# 608_donkey_030101_AllDirections.net
KiCad netlist of a schematic drawn in EAGLE
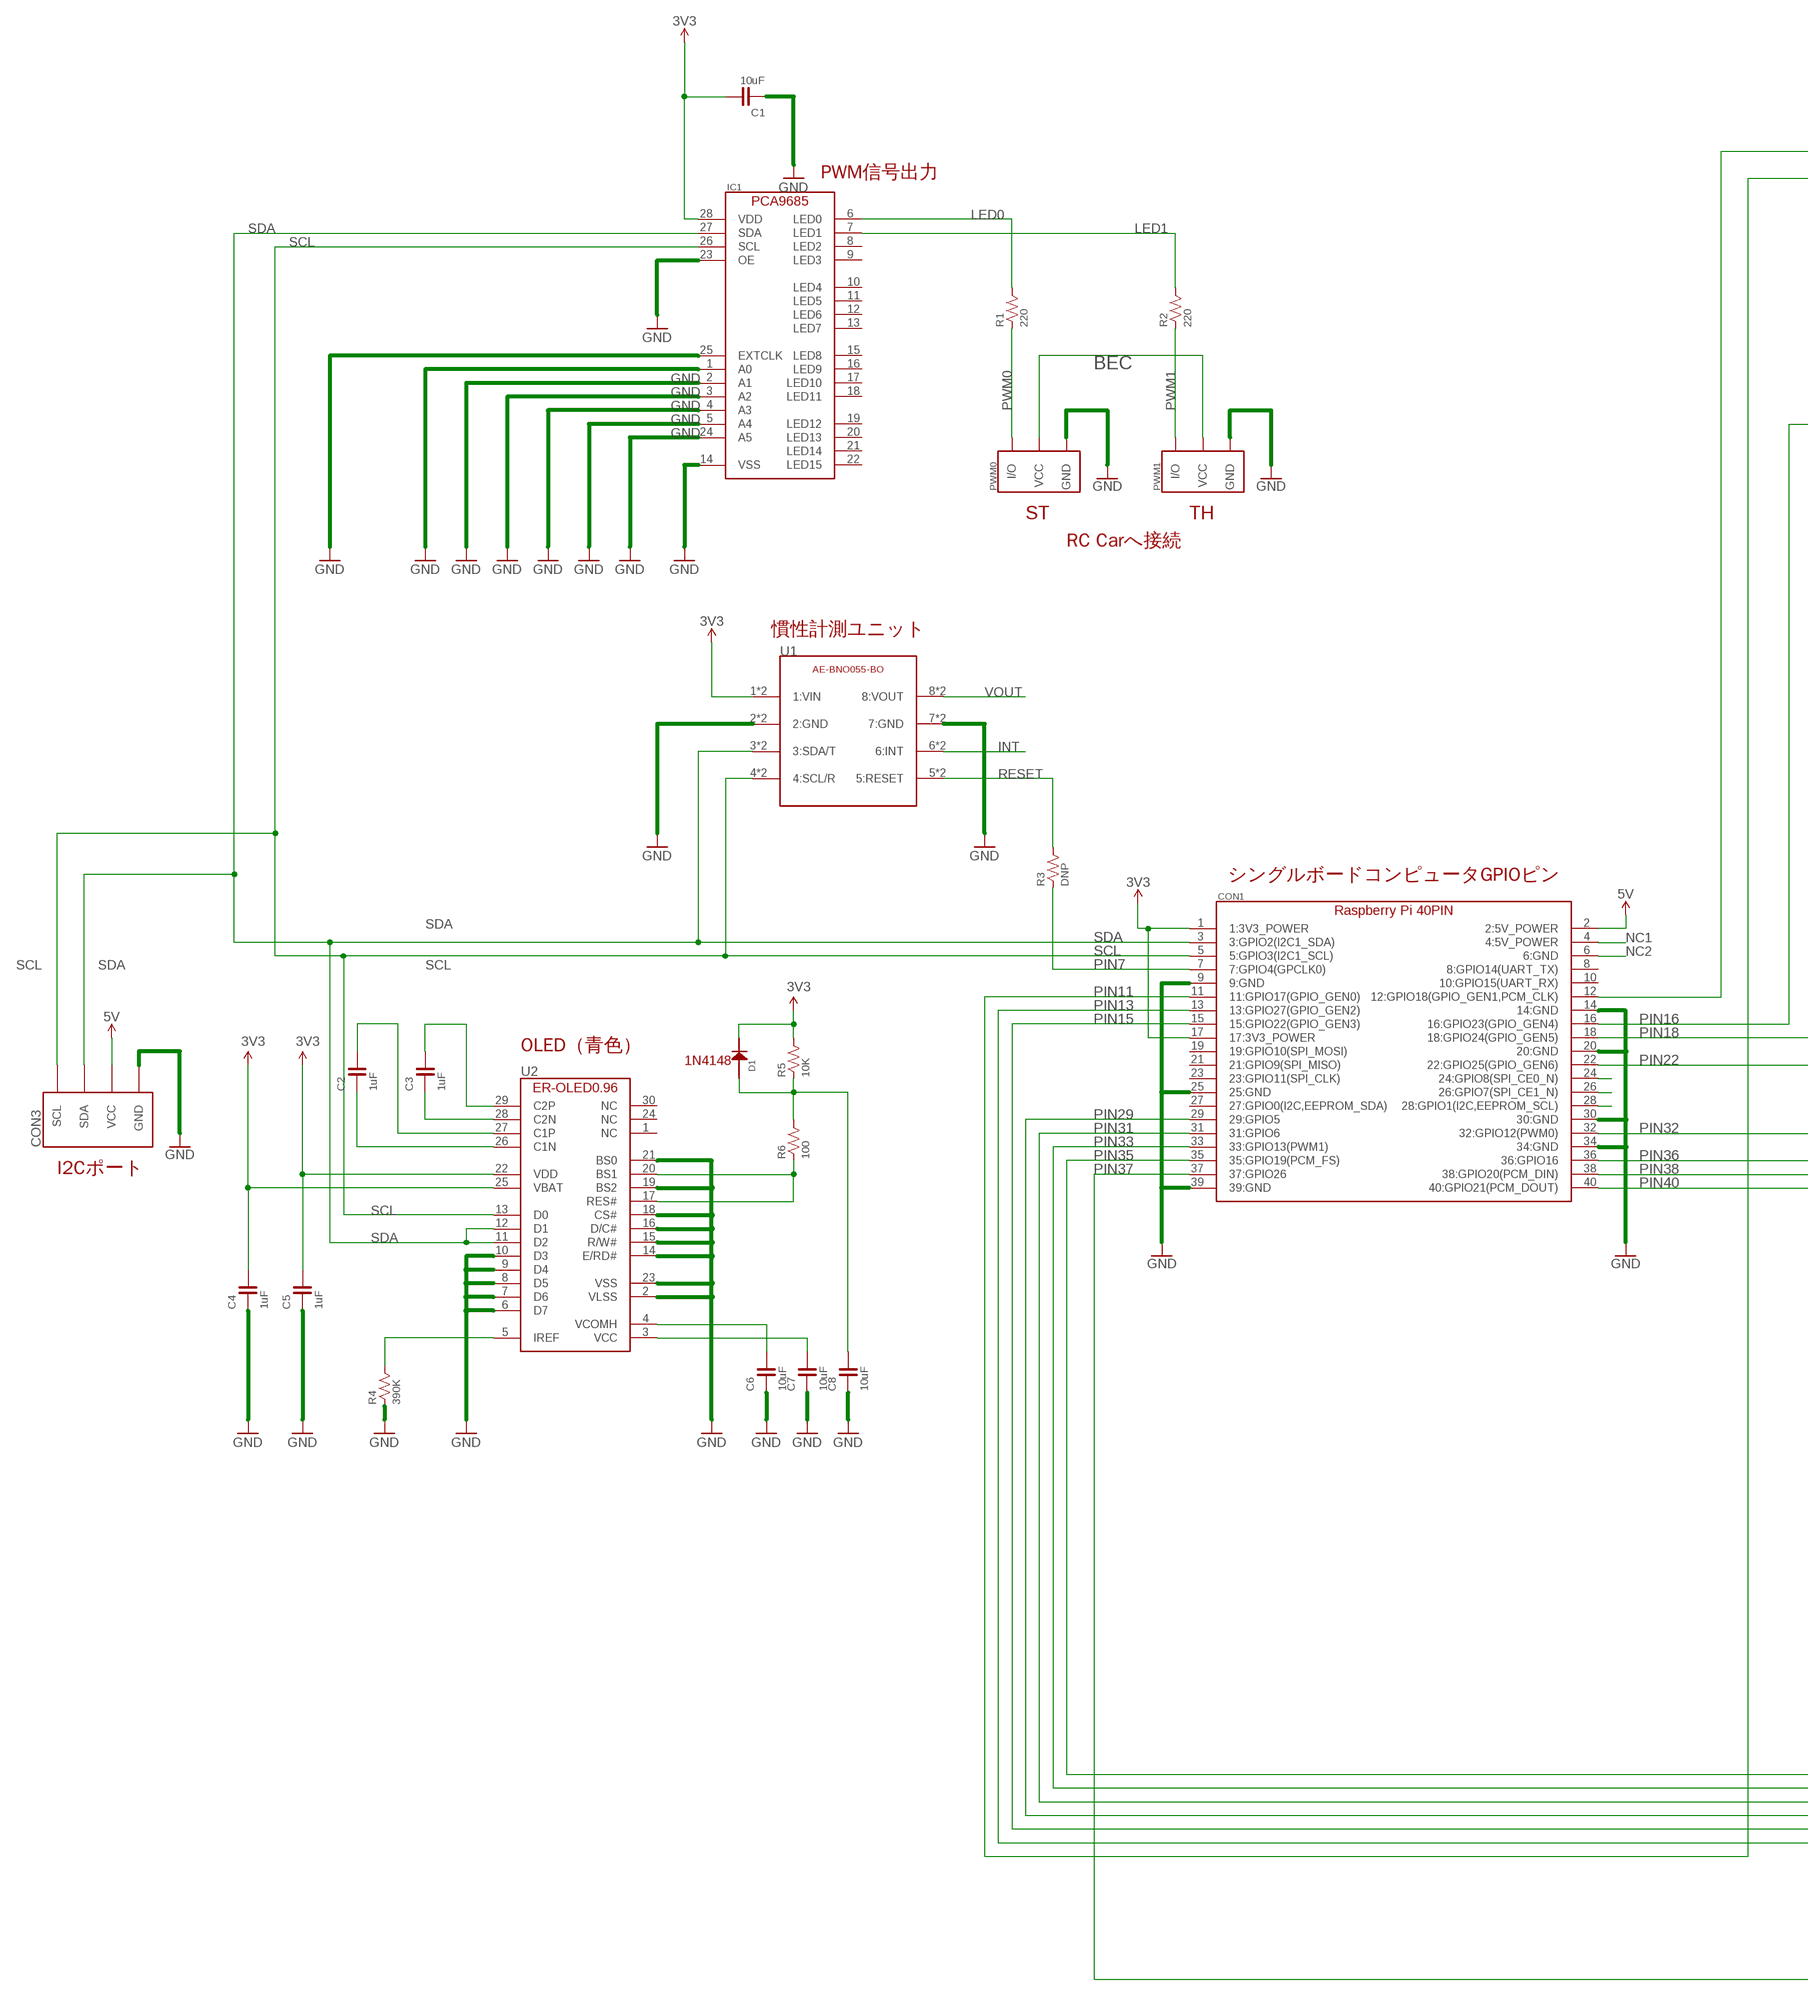
[diagram p0: schematic, sheet 1, part 1 of 3]
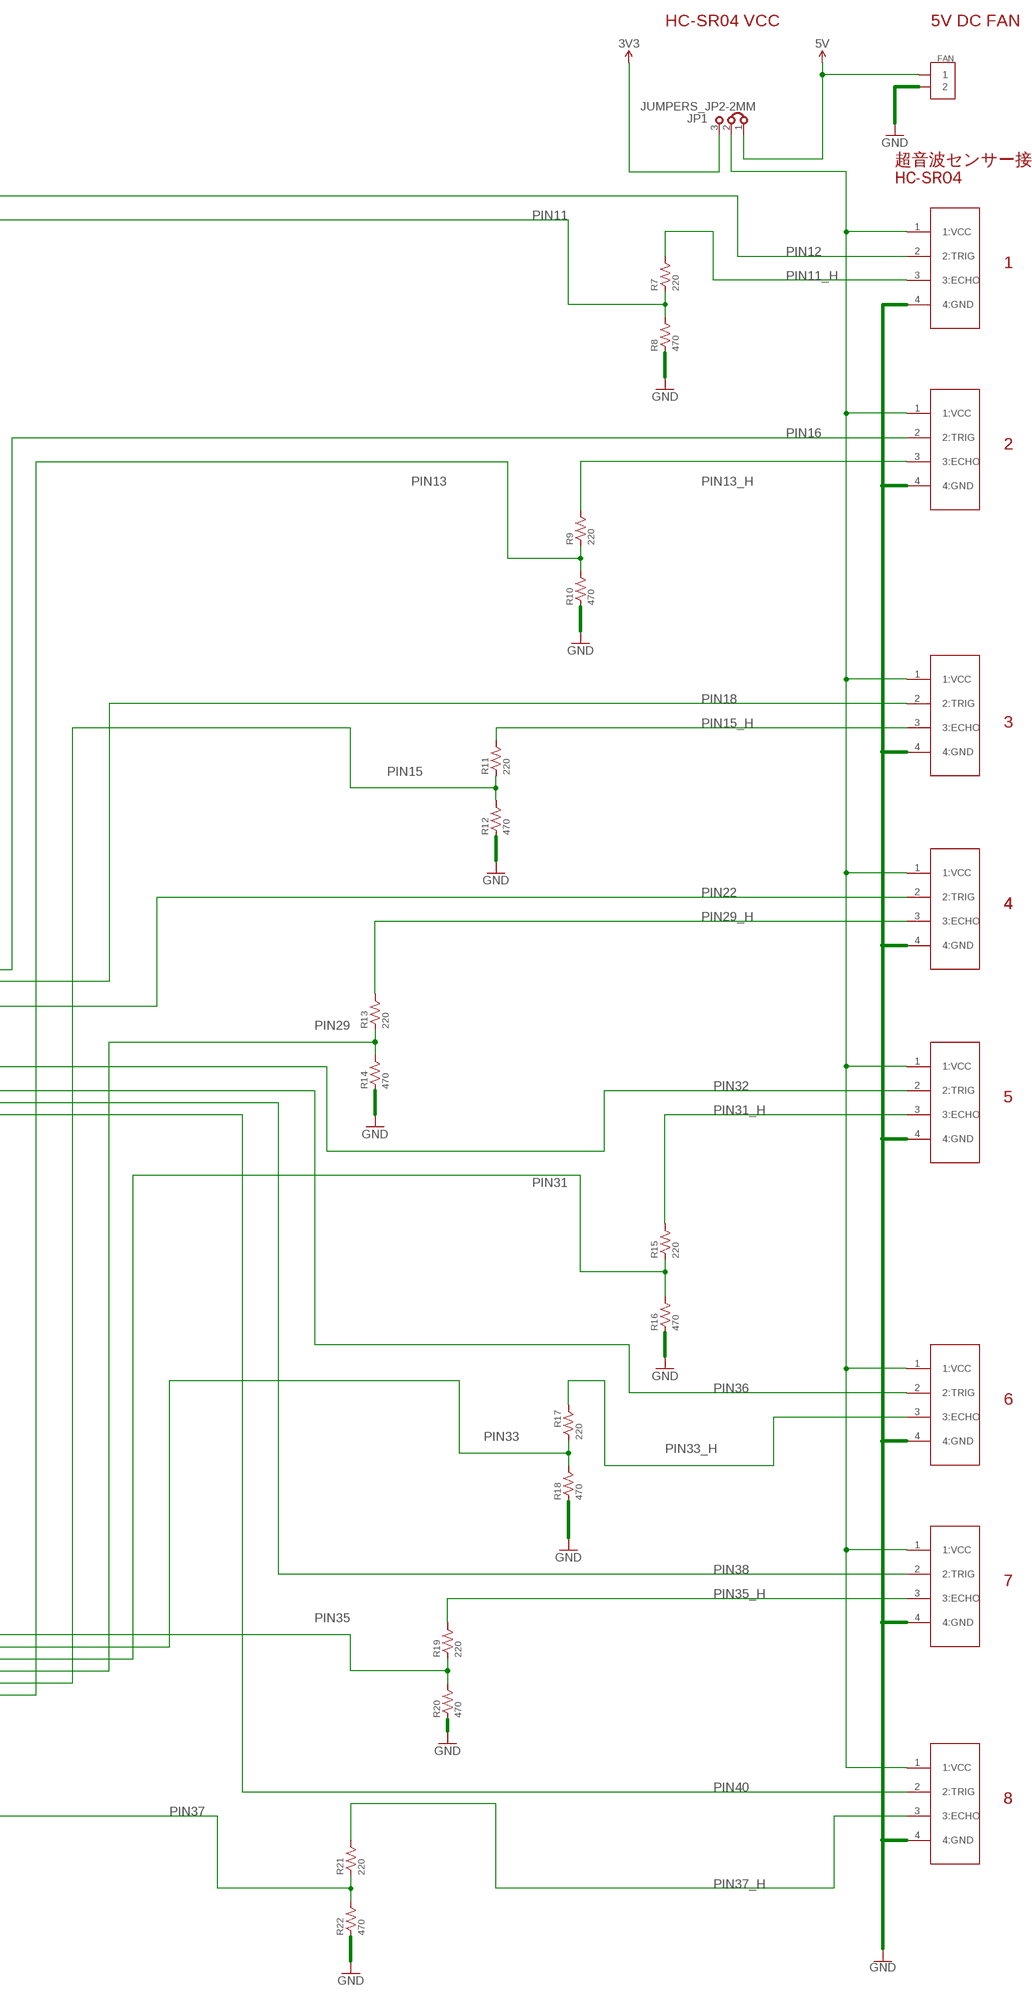
[diagram p1: schematic, sheet 1, part 2 of 3]
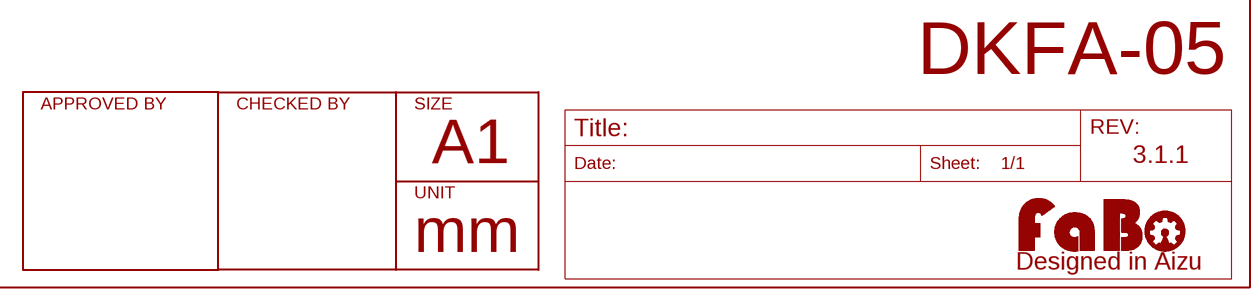
[diagram p2: schematic, sheet 1, part 3 of 3]

(export (version "E")
  (design (tool "Eeschema 10.0.6"))
  (components
    (comp (ref "C1")
      (value "10uF")
      (footprint "eagle-import:0603")
      (libsource (lib "eagle-import") (part "CAPACITOR-0603"))
    )
    (comp (ref "C2")
      (value "1uF")
      (footprint "eagle-import:0603-BOTTOM")
      (libsource (lib "eagle-import") (part "CAPACITOR-0603-BOTTOM"))
    )
    (comp (ref "C3")
      (value "1uF")
      (footprint "eagle-import:0603-BOTTOM")
      (libsource (lib "eagle-import") (part "CAPACITOR-0603-BOTTOM"))
    )
    (comp (ref "C4")
      (value "1uF")
      (footprint "eagle-import:0603-BOTTOM")
      (libsource (lib "eagle-import") (part "CAPACITOR-0603-BOTTOM"))
    )
    (comp (ref "C5")
      (value "1uF")
      (footprint "eagle-import:0603-BOTTOM")
      (libsource (lib "eagle-import") (part "CAPACITOR-0603-BOTTOM"))
    )
    (comp (ref "C6")
      (value "10uF")
      (footprint "eagle-import:0603-BOTTOM")
      (libsource (lib "eagle-import") (part "CAPACITOR-0603-BOTTOM"))
    )
    (comp (ref "C7")
      (value "10uF")
      (footprint "eagle-import:0603-BOTTOM")
      (libsource (lib "eagle-import") (part "CAPACITOR-0603-BOTTOM"))
    )
    (comp (ref "C8")
      (value "10uF")
      (footprint "eagle-import:0603-BOTTOM")
      (libsource (lib "eagle-import") (part "CAPACITOR-0603-BOTTOM"))
    )
    (comp (ref "CON1")
      (value "RASPBERRYPI_SHEILD")
      (footprint "eagle-import:RASPBERRY_PI_SHILED")
      (libsource (lib "eagle-import") (part "RASPBERRYPI_SHEILD"))
    )
    (comp (ref "CON3")
      (value "FABO_BRICK_I2C-S04B-PASK-2")
      (footprint "eagle-import:FABO_BRICK_I2C_S04B-PASK-2")
      (libsource (lib "eagle-import") (part "FABO_BRICK_I2C-S04B-PASK-2"))
    )
    (comp (ref "D1")
      (value "1N4148")
      (footprint "eagle-import:1N4148W")
      (libsource (lib "eagle-import") (part "1N4148"))
    )
    (comp (ref "FAN")
      (value "PIN_1X2")
      (footprint "eagle-import:PIN_1X2")
      (libsource (lib "eagle-import") (part "PIN_1X2"))
    )
    (comp (ref "HC1")
      (value "HC-SR04CONHS-SR04CON-SPEACING")
      (footprint "eagle-import:HC-SR04CON-SPEACE")
      (libsource (lib "eagle-import") (part "HC-SR04CONHS-SR04CON-SPEACING"))
    )
    (comp (ref "HC2")
      (value "HC-SR04CONHS-SR04CON-SPEACING")
      (footprint "eagle-import:HC-SR04CON-SPEACE")
      (libsource (lib "eagle-import") (part "HC-SR04CONHS-SR04CON-SPEACING"))
    )
    (comp (ref "HC3")
      (value "HC-SR04CONHS-SR04CON-SPEACING")
      (footprint "eagle-import:HC-SR04CON-SPEACE")
      (libsource (lib "eagle-import") (part "HC-SR04CONHS-SR04CON-SPEACING"))
    )
    (comp (ref "HC4")
      (value "HC-SR04CONHS-SR04CON-SPEACING")
      (footprint "eagle-import:HC-SR04CON-SPEACE")
      (libsource (lib "eagle-import") (part "HC-SR04CONHS-SR04CON-SPEACING"))
    )
    (comp (ref "HC5")
      (value "HC-SR04CONHS-SR04CON-SPEACING")
      (footprint "eagle-import:HC-SR04CON-SPEACE")
      (libsource (lib "eagle-import") (part "HC-SR04CONHS-SR04CON-SPEACING"))
    )
    (comp (ref "HC6")
      (value "HC-SR04CONHS-SR04CON-SPEACING")
      (footprint "eagle-import:HC-SR04CON-SPEACE")
      (libsource (lib "eagle-import") (part "HC-SR04CONHS-SR04CON-SPEACING"))
    )
    (comp (ref "HC7")
      (value "HC-SR04CONHS-SR04CON-SPEACING")
      (footprint "eagle-import:HC-SR04CON-SPEACE")
      (libsource (lib "eagle-import") (part "HC-SR04CONHS-SR04CON-SPEACING"))
    )
    (comp (ref "HC8")
      (value "HC-SR04CONHS-SR04CON-SPEACING")
      (footprint "eagle-import:HC-SR04CON-SPEACE")
      (libsource (lib "eagle-import") (part "HC-SR04CONHS-SR04CON-SPEACING"))
    )
    (comp (ref "IC1")
      (value "PCA9685BS")
      (footprint "eagle-import:PCA9685")
      (libsource (lib "eagle-import") (part "PCA9685BS"))
    )
    (comp (ref "JP1")
      (value "JUMPERS_JP2-2MM")
      (footprint "eagle-import:JUMPERS_JP2-2MM")
      (libsource (lib "eagle-import") (part "JUMPERS_JP2-2MM"))
    )
    (comp (ref "LOGO1")
      (value "LOGO_FABO-M")
      (footprint "eagle-import:LOGO_FABO_M")
      (libsource (lib "eagle-import") (part "LOGO_FABO-M"))
    )
    (comp (ref "PWM0")
      (value "PWM0")
      (footprint "eagle-import:PIN_1X3_NARROW")
      (libsource (lib "eagle-import") (part "FABO-BRICK-3PIN_HEADER"))
    )
    (comp (ref "PWM1")
      (value "PWM1")
      (footprint "eagle-import:PIN_1X3_NARROW")
      (libsource (lib "eagle-import") (part "FABO-BRICK-3PIN_HEADER"))
    )
    (comp (ref "R1")
      (value "220")
      (footprint "eagle-import:0603")
      (libsource (lib "eagle-import") (part "RESISTOR-0603"))
    )
    (comp (ref "R2")
      (value "220")
      (footprint "eagle-import:0603")
      (libsource (lib "eagle-import") (part "RESISTOR-0603"))
    )
    (comp (ref "R3")
      (value "DNP")
      (footprint "eagle-import:0603-BOTTOM")
      (libsource (lib "eagle-import") (part "RESISTOR-0603-BOTTOM"))
    )
    (comp (ref "R4")
      (value "390K")
      (footprint "eagle-import:0603-BOTTOM")
      (libsource (lib "eagle-import") (part "RESISTOR-0603-BOTTOM"))
    )
    (comp (ref "R5")
      (value "10K")
      (footprint "eagle-import:0603-BOTTOM")
      (libsource (lib "eagle-import") (part "RESISTOR-0603-BOTTOM"))
    )
    (comp (ref "R6")
      (value "100")
      (footprint "eagle-import:0603-BOTTOM")
      (libsource (lib "eagle-import") (part "RESISTOR-0603-BOTTOM"))
    )
    (comp (ref "R7")
      (value "220")
      (footprint "eagle-import:0603")
      (libsource (lib "eagle-import") (part "RESISTOR-0603"))
    )
    (comp (ref "R8")
      (value "470")
      (footprint "eagle-import:0603")
      (libsource (lib "eagle-import") (part "RESISTOR-0603"))
    )
    (comp (ref "R9")
      (value "220")
      (footprint "eagle-import:0603")
      (libsource (lib "eagle-import") (part "RESISTOR-0603"))
    )
    (comp (ref "R10")
      (value "470")
      (footprint "eagle-import:0603")
      (libsource (lib "eagle-import") (part "RESISTOR-0603"))
    )
    (comp (ref "R11")
      (value "220")
      (footprint "eagle-import:0603")
      (libsource (lib "eagle-import") (part "RESISTOR-0603"))
    )
    (comp (ref "R12")
      (value "470")
      (footprint "eagle-import:0603")
      (libsource (lib "eagle-import") (part "RESISTOR-0603"))
    )
    (comp (ref "R13")
      (value "220")
      (footprint "eagle-import:0603")
      (libsource (lib "eagle-import") (part "RESISTOR-0603"))
    )
    (comp (ref "R14")
      (value "470")
      (footprint "eagle-import:0603")
      (libsource (lib "eagle-import") (part "RESISTOR-0603"))
    )
    (comp (ref "R15")
      (value "220")
      (footprint "eagle-import:0603")
      (libsource (lib "eagle-import") (part "RESISTOR-0603"))
    )
    (comp (ref "R16")
      (value "470")
      (footprint "eagle-import:0603")
      (libsource (lib "eagle-import") (part "RESISTOR-0603"))
    )
    (comp (ref "R17")
      (value "220")
      (footprint "eagle-import:0603")
      (libsource (lib "eagle-import") (part "RESISTOR-0603"))
    )
    (comp (ref "R18")
      (value "470")
      (footprint "eagle-import:0603")
      (libsource (lib "eagle-import") (part "RESISTOR-0603"))
    )
    (comp (ref "R19")
      (value "220")
      (footprint "eagle-import:0603")
      (libsource (lib "eagle-import") (part "RESISTOR-0603"))
    )
    (comp (ref "R20")
      (value "470")
      (footprint "eagle-import:0603")
      (libsource (lib "eagle-import") (part "RESISTOR-0603"))
    )
    (comp (ref "R21")
      (value "220")
      (footprint "eagle-import:0603")
      (libsource (lib "eagle-import") (part "RESISTOR-0603"))
    )
    (comp (ref "R22")
      (value "470")
      (footprint "eagle-import:0603")
      (libsource (lib "eagle-import") (part "RESISTOR-0603"))
    )
    (comp (ref "U1")
      (value "AE-BNO055-BO")
      (footprint "eagle-import:DIP_8")
      (libsource (lib "eagle-import") (part "AE-BNO055-BO"))
    )
    (comp (ref "U2")
      (value "ER-OLED0.96-1ER-CON30HT-1_REV2")
      (footprint "eagle-import:ER-CON30HT-1_REV2")
      (libsource (lib "eagle-import") (part "ER-OLED0.96-1ER-CON30HT-1_REV2"))
    )
  )
  (nets
    (net (code "1") (name "/BEC") (class "Default")
      (node (ref "PWM0") (pin "2") (pinfunction "VCC_2") (pintype "bidirectional"))
      (node (ref "PWM1") (pin "2") (pinfunction "VCC_2") (pintype "bidirectional"))
    )
    (net (code "2") (name "/INT") (class "Default")
      (node (ref "U1") (pin "6") (pinfunction "6:INT_6") (pintype "output"))
      (node (ref "U1") (pin "6-1") (pinfunction "6:INT_6-1") (pintype "output"))
    )
    (net (code "3") (name "/LED0") (class "Default")
      (node (ref "IC1") (pin "6") (pinfunction "LED0_6") (pintype "bidirectional"))
      (node (ref "R1") (pin "2") (pinfunction "2_2") (pintype "bidirectional"))
    )
    (net (code "4") (name "/LED1") (class "Default")
      (node (ref "IC1") (pin "7") (pinfunction "LED1_7") (pintype "bidirectional"))
      (node (ref "R2") (pin "2") (pinfunction "2_2") (pintype "bidirectional"))
    )
    (net (code "5") (name "/NC1") (class "Default")
      (node (ref "CON1") (pin "4") (pinfunction "4:5V_POWER_4") (pintype "power_in"))
    )
    (net (code "6") (name "/NC2") (class "Default")
      (node (ref "CON1") (pin "6") (pinfunction "6:GND_6") (pintype "power_in"))
    )
    (net (code "7") (name "/PIN7") (class "Default")
      (node (ref "CON1") (pin "7") (pinfunction "7:GPIO4(GPCLK0)_7") (pintype "bidirectional"))
      (node (ref "R3") (pin "1") (pinfunction "1_1") (pintype "bidirectional"))
    )
    (net (code "8") (name "/PIN11") (class "Default")
      (node (ref "CON1") (pin "11") (pinfunction "11:GPIO17(GPIO_GEN0)_11") (pintype "bidirectional"))
      (node (ref "R7") (pin "1") (pinfunction "1_1") (pintype "bidirectional"))
      (node (ref "R8") (pin "2") (pinfunction "2_2") (pintype "bidirectional"))
    )
    (net (code "9") (name "/PIN11_H") (class "Default")
      (node (ref "HC1") (pin "3") (pinfunction "3:ECHO_3") (pintype "bidirectional"))
      (node (ref "R7") (pin "2") (pinfunction "2_2") (pintype "bidirectional"))
    )
    (net (code "10") (name "/PIN12") (class "Default")
      (node (ref "CON1") (pin "12") (pinfunction "12:GPIO18(GPIO_GEN1,PCM_CLK)_12") (pintype "bidirectional"))
      (node (ref "HC1") (pin "2") (pinfunction "2:TRIG_2") (pintype "bidirectional"))
    )
    (net (code "11") (name "/PIN13") (class "Default")
      (node (ref "CON1") (pin "13") (pinfunction "13:GPIO27(GPIO_GEN2)_13") (pintype "bidirectional"))
      (node (ref "R10") (pin "2") (pinfunction "2_2") (pintype "bidirectional"))
      (node (ref "R9") (pin "1") (pinfunction "1_1") (pintype "bidirectional"))
    )
    (net (code "12") (name "/PIN13_H") (class "Default")
      (node (ref "HC2") (pin "3") (pinfunction "3:ECHO_3") (pintype "bidirectional"))
      (node (ref "R9") (pin "2") (pinfunction "2_2") (pintype "bidirectional"))
    )
    (net (code "13") (name "/PIN15") (class "Default")
      (node (ref "CON1") (pin "15") (pinfunction "15:GPIO22(GPIO_GEN3)_15") (pintype "bidirectional"))
      (node (ref "R11") (pin "1") (pinfunction "1_1") (pintype "bidirectional"))
      (node (ref "R12") (pin "2") (pinfunction "2_2") (pintype "bidirectional"))
    )
    (net (code "14") (name "/PIN15_H") (class "Default")
      (node (ref "HC3") (pin "3") (pinfunction "3:ECHO_3") (pintype "bidirectional"))
      (node (ref "R11") (pin "2") (pinfunction "2_2") (pintype "bidirectional"))
    )
    (net (code "15") (name "/PIN16") (class "Default")
      (node (ref "CON1") (pin "16") (pinfunction "16:GPIO23(GPIO_GEN4)_16") (pintype "bidirectional"))
      (node (ref "HC2") (pin "2") (pinfunction "2:TRIG_2") (pintype "bidirectional"))
    )
    (net (code "16") (name "/PIN18") (class "Default")
      (node (ref "CON1") (pin "18") (pinfunction "18:GPIO24(GPIO_GEN5)_18") (pintype "bidirectional"))
      (node (ref "HC3") (pin "2") (pinfunction "2:TRIG_2") (pintype "bidirectional"))
    )
    (net (code "17") (name "/PIN22") (class "Default")
      (node (ref "CON1") (pin "22") (pinfunction "22:GPIO25(GPIO_GEN6)_22") (pintype "bidirectional"))
      (node (ref "HC4") (pin "2") (pinfunction "2:TRIG_2") (pintype "bidirectional"))
    )
    (net (code "18") (name "/PIN29") (class "Default")
      (node (ref "CON1") (pin "29") (pinfunction "29:GPIO5_29") (pintype "bidirectional"))
      (node (ref "R13") (pin "1") (pinfunction "1_1") (pintype "bidirectional"))
      (node (ref "R14") (pin "2") (pinfunction "2_2") (pintype "bidirectional"))
    )
    (net (code "19") (name "/PIN29_H") (class "Default")
      (node (ref "HC4") (pin "3") (pinfunction "3:ECHO_3") (pintype "bidirectional"))
      (node (ref "R13") (pin "2") (pinfunction "2_2") (pintype "bidirectional"))
    )
    (net (code "20") (name "/PIN31") (class "Default")
      (node (ref "CON1") (pin "31") (pinfunction "31:GPIO6_31") (pintype "bidirectional"))
      (node (ref "R15") (pin "1") (pinfunction "1_1") (pintype "bidirectional"))
      (node (ref "R16") (pin "2") (pinfunction "2_2") (pintype "bidirectional"))
    )
    (net (code "21") (name "/PIN31_H") (class "Default")
      (node (ref "HC5") (pin "3") (pinfunction "3:ECHO_3") (pintype "bidirectional"))
      (node (ref "R15") (pin "2") (pinfunction "2_2") (pintype "bidirectional"))
    )
    (net (code "22") (name "/PIN32") (class "Default")
      (node (ref "CON1") (pin "32") (pinfunction "32:GPIO12(PWM0)_32") (pintype "bidirectional"))
      (node (ref "HC5") (pin "2") (pinfunction "2:TRIG_2") (pintype "bidirectional"))
    )
    (net (code "23") (name "/PIN33") (class "Default")
      (node (ref "CON1") (pin "33") (pinfunction "33:GPIO13(PWM1)_33") (pintype "bidirectional"))
      (node (ref "R17") (pin "1") (pinfunction "1_1") (pintype "bidirectional"))
      (node (ref "R18") (pin "2") (pinfunction "2_2") (pintype "bidirectional"))
    )
    (net (code "24") (name "/PIN33_H") (class "Default")
      (node (ref "HC6") (pin "3") (pinfunction "3:ECHO_3") (pintype "bidirectional"))
      (node (ref "R17") (pin "2") (pinfunction "2_2") (pintype "bidirectional"))
    )
    (net (code "25") (name "/PIN35") (class "Default")
      (node (ref "CON1") (pin "35") (pinfunction "35:GPIO19(PCM_FS)_35") (pintype "bidirectional"))
      (node (ref "R19") (pin "1") (pinfunction "1_1") (pintype "bidirectional"))
      (node (ref "R20") (pin "2") (pinfunction "2_2") (pintype "bidirectional"))
    )
    (net (code "26") (name "/PIN35_H") (class "Default")
      (node (ref "HC7") (pin "3") (pinfunction "3:ECHO_3") (pintype "bidirectional"))
      (node (ref "R19") (pin "2") (pinfunction "2_2") (pintype "bidirectional"))
    )
    (net (code "27") (name "/PIN36") (class "Default")
      (node (ref "CON1") (pin "36") (pinfunction "36:GPIO16_36") (pintype "bidirectional"))
      (node (ref "HC6") (pin "2") (pinfunction "2:TRIG_2") (pintype "bidirectional"))
    )
    (net (code "28") (name "/PIN37") (class "Default")
      (node (ref "CON1") (pin "37") (pinfunction "37:GPIO26_37") (pintype "bidirectional"))
      (node (ref "R21") (pin "1") (pinfunction "1_1") (pintype "bidirectional"))
      (node (ref "R22") (pin "2") (pinfunction "2_2") (pintype "bidirectional"))
    )
    (net (code "29") (name "/PIN37_H") (class "Default")
      (node (ref "HC8") (pin "3") (pinfunction "3:ECHO_3") (pintype "bidirectional"))
      (node (ref "R21") (pin "2") (pinfunction "2_2") (pintype "bidirectional"))
    )
    (net (code "30") (name "/PIN38") (class "Default")
      (node (ref "CON1") (pin "38") (pinfunction "38:GPIO20(PCM_DIN)_38") (pintype "bidirectional"))
      (node (ref "HC7") (pin "2") (pinfunction "2:TRIG_2") (pintype "bidirectional"))
    )
    (net (code "31") (name "/PIN40") (class "Default")
      (node (ref "CON1") (pin "40") (pinfunction "40:GPIO21(PCM_DOUT)_40") (pintype "bidirectional"))
      (node (ref "HC8") (pin "2") (pinfunction "2:TRIG_2") (pintype "bidirectional"))
    )
    (net (code "32") (name "/PWM0") (class "Default")
      (node (ref "PWM0") (pin "1") (pinfunction "I/O_1") (pintype "bidirectional"))
      (node (ref "R1") (pin "1") (pinfunction "1_1") (pintype "bidirectional"))
    )
    (net (code "33") (name "/PWM1") (class "Default")
      (node (ref "PWM1") (pin "1") (pinfunction "I/O_1") (pintype "bidirectional"))
      (node (ref "R2") (pin "1") (pinfunction "1_1") (pintype "bidirectional"))
    )
    (net (code "34") (name "/RESET") (class "Default")
      (node (ref "R3") (pin "2") (pinfunction "2_2") (pintype "bidirectional"))
      (node (ref "U1") (pin "5") (pinfunction "5:RESET_5") (pintype "input"))
      (node (ref "U1") (pin "5-1") (pinfunction "5:RESET_5-1") (pintype "input"))
    )
    (net (code "35") (name "/SCL") (class "Default")
      (node (ref "CON1") (pin "5") (pinfunction "5:GPIO3(I2C1_SCL)_5") (pintype "bidirectional"))
      (node (ref "CON3") (pin "SCL") (pinfunction "SCL_SCL") (pintype "bidirectional"))
      (node (ref "IC1") (pin "26") (pinfunction "SCL_26") (pintype "bidirectional"))
      (node (ref "U1") (pin "4") (pinfunction "4:SCL/R_4") (pintype "bidirectional"))
      (node (ref "U1") (pin "4-1") (pinfunction "4:SCL/R_4-1") (pintype "bidirectional"))
      (node (ref "U2") (pin "13") (pinfunction "D0_13") (pintype "bidirectional"))
    )
    (net (code "36") (name "/SDA") (class "Default")
      (node (ref "CON1") (pin "3") (pinfunction "3:GPIO2(I2C1_SDA)_3") (pintype "bidirectional"))
      (node (ref "CON3") (pin "SDA") (pinfunction "SDA_SDA") (pintype "bidirectional"))
      (node (ref "IC1") (pin "27") (pinfunction "SDA_27") (pintype "bidirectional"))
      (node (ref "U1") (pin "3") (pinfunction "3:SDA/T_3") (pintype "bidirectional"))
      (node (ref "U1") (pin "3-1") (pinfunction "3:SDA/T_3-1") (pintype "bidirectional"))
      (node (ref "U2") (pin "11") (pinfunction "D2_11") (pintype "bidirectional"))
      (node (ref "U2") (pin "12") (pinfunction "D1_12") (pintype "bidirectional"))
    )
    (net (code "37") (name "/VOUT") (class "Default")
      (node (ref "U1") (pin "8") (pinfunction "8:VOUT_8") (pintype "power_in"))
      (node (ref "U1") (pin "8-1") (pinfunction "8:VOUT_8-1") (pintype "power_in"))
    )
    (net (code "38") (name "3V3") (class "Default")
      (node (ref "C1") (pin "2") (pinfunction "2_2") (pintype "passive"))
      (node (ref "C4") (pin "2") (pinfunction "2_2") (pintype "passive"))
      (node (ref "C5") (pin "2") (pinfunction "2_2") (pintype "passive"))
      (node (ref "CON1") (pin "1") (pinfunction "1:3V3_POWER_1") (pintype "power_in"))
      (node (ref "CON1") (pin "17") (pinfunction "17:3V3_POWER_17") (pintype "power_in"))
      (node (ref "D1") (pin "CATHODE") (pinfunction "CATHODE_CATHODE") (pintype "bidirectional"))
      (node (ref "IC1") (pin "28") (pinfunction "VDD_28") (pintype "bidirectional"))
      (node (ref "JP1") (pin "3") (pinfunction "3_3") (pintype "passive"))
      (node (ref "R5") (pin "2") (pinfunction "2_2") (pintype "bidirectional"))
      (node (ref "U1") (pin "1") (pinfunction "1:VIN_1") (pintype "power_in"))
      (node (ref "U1") (pin "1-1") (pinfunction "1:VIN_1-1") (pintype "power_in"))
      (node (ref "U2") (pin "22") (pinfunction "VDD_22") (pintype "bidirectional"))
      (node (ref "U2") (pin "25") (pinfunction "VBAT_25") (pintype "bidirectional"))
    )
    (net (code "39") (name "5V") (class "Default")
      (node (ref "CON1") (pin "2") (pinfunction "2:5V_POWER_2") (pintype "power_in"))
      (node (ref "CON3") (pin "VCC") (pinfunction "VCC_VCC") (pintype "bidirectional"))
      (node (ref "FAN") (pin "1") (pinfunction "1_1") (pintype "bidirectional"))
      (node (ref "JP1") (pin "1") (pinfunction "1_1") (pintype "passive"))
    )
    (net (code "40") (name "GND") (class "Default")
      (node (ref "C1") (pin "1") (pinfunction "1_1") (pintype "passive"))
      (node (ref "C4") (pin "1") (pinfunction "1_1") (pintype "passive"))
      (node (ref "C5") (pin "1") (pinfunction "1_1") (pintype "passive"))
      (node (ref "C6") (pin "1") (pinfunction "1_1") (pintype "passive"))
      (node (ref "C7") (pin "1") (pinfunction "1_1") (pintype "passive"))
      (node (ref "C8") (pin "1") (pinfunction "1_1") (pintype "passive"))
      (node (ref "CON1") (pin "14") (pinfunction "14:GND_14") (pintype "power_in"))
      (node (ref "CON1") (pin "20") (pinfunction "20:GND_20") (pintype "power_in"))
      (node (ref "CON1") (pin "25") (pinfunction "25:GND_25") (pintype "power_in"))
      (node (ref "CON1") (pin "30") (pinfunction "30:GND_30") (pintype "power_in"))
      (node (ref "CON1") (pin "34") (pinfunction "34:GND_34") (pintype "power_in"))
      (node (ref "CON1") (pin "39") (pinfunction "39:GND_39") (pintype "power_in"))
      (node (ref "CON1") (pin "9") (pinfunction "9:GND_9") (pintype "power_in"))
      (node (ref "CON3") (pin "GND") (pinfunction "GND_GND") (pintype "bidirectional"))
      (node (ref "FAN") (pin "2") (pinfunction "2_2") (pintype "bidirectional"))
      (node (ref "HC1") (pin "4") (pinfunction "4:GND_4") (pintype "bidirectional"))
      (node (ref "HC2") (pin "4") (pinfunction "4:GND_4") (pintype "bidirectional"))
      (node (ref "HC3") (pin "4") (pinfunction "4:GND_4") (pintype "bidirectional"))
      (node (ref "HC4") (pin "4") (pinfunction "4:GND_4") (pintype "bidirectional"))
      (node (ref "HC5") (pin "4") (pinfunction "4:GND_4") (pintype "bidirectional"))
      (node (ref "HC6") (pin "4") (pinfunction "4:GND_4") (pintype "bidirectional"))
      (node (ref "HC7") (pin "4") (pinfunction "4:GND_4") (pintype "bidirectional"))
      (node (ref "HC8") (pin "4") (pinfunction "4:GND_4") (pintype "bidirectional"))
      (node (ref "IC1") (pin "1") (pinfunction "A0_1") (pintype "bidirectional"))
      (node (ref "IC1") (pin "14") (pinfunction "VSS_14") (pintype "bidirectional"))
      (node (ref "IC1") (pin "2") (pinfunction "A1_2") (pintype "bidirectional"))
      (node (ref "IC1") (pin "23") (pinfunction "OE_23") (pintype "bidirectional"))
      (node (ref "IC1") (pin "24") (pinfunction "A5_24") (pintype "bidirectional"))
      (node (ref "IC1") (pin "25") (pinfunction "EXTCLK_25") (pintype "bidirectional"))
      (node (ref "IC1") (pin "3") (pinfunction "A2_3") (pintype "bidirectional"))
      (node (ref "IC1") (pin "4") (pinfunction "A3_4") (pintype "bidirectional"))
      (node (ref "IC1") (pin "5") (pinfunction "A4_5") (pintype "bidirectional"))
      (node (ref "PWM0") (pin "3") (pinfunction "GND_3") (pintype "bidirectional"))
      (node (ref "PWM1") (pin "3") (pinfunction "GND_3") (pintype "bidirectional"))
      (node (ref "R10") (pin "1") (pinfunction "1_1") (pintype "bidirectional"))
      (node (ref "R12") (pin "1") (pinfunction "1_1") (pintype "bidirectional"))
      (node (ref "R14") (pin "1") (pinfunction "1_1") (pintype "bidirectional"))
      (node (ref "R16") (pin "1") (pinfunction "1_1") (pintype "bidirectional"))
      (node (ref "R18") (pin "1") (pinfunction "1_1") (pintype "bidirectional"))
      (node (ref "R20") (pin "1") (pinfunction "1_1") (pintype "bidirectional"))
      (node (ref "R22") (pin "1") (pinfunction "1_1") (pintype "bidirectional"))
      (node (ref "R4") (pin "1") (pinfunction "1_1") (pintype "bidirectional"))
      (node (ref "R8") (pin "1") (pinfunction "1_1") (pintype "bidirectional"))
      (node (ref "U1") (pin "2") (pinfunction "2:GND_2") (pintype "power_in"))
      (node (ref "U1") (pin "2-1") (pinfunction "2:GND_2-1") (pintype "power_in"))
      (node (ref "U1") (pin "7") (pinfunction "7:GND_7") (pintype "power_in"))
      (node (ref "U1") (pin "7-1") (pinfunction "7:GND_7-1") (pintype "power_in"))
      (node (ref "U2") (pin "10") (pinfunction "D3_10") (pintype "bidirectional"))
      (node (ref "U2") (pin "14") (pinfunction "E/RD#_14") (pintype "bidirectional"))
      (node (ref "U2") (pin "15") (pinfunction "R/W#_15") (pintype "bidirectional"))
      (node (ref "U2") (pin "16") (pinfunction "D/C#_16") (pintype "bidirectional"))
      (node (ref "U2") (pin "18") (pinfunction "CS#_18") (pintype "bidirectional"))
      (node (ref "U2") (pin "19") (pinfunction "BS2_19") (pintype "bidirectional"))
      (node (ref "U2") (pin "2") (pinfunction "VLSS_2") (pintype "bidirectional"))
      (node (ref "U2") (pin "21") (pinfunction "BS0_21") (pintype "bidirectional"))
      (node (ref "U2") (pin "23") (pinfunction "VSS_23") (pintype "bidirectional"))
      (node (ref "U2") (pin "6") (pinfunction "D7_6") (pintype "bidirectional"))
      (node (ref "U2") (pin "7") (pinfunction "D6_7") (pintype "bidirectional"))
      (node (ref "U2") (pin "8") (pinfunction "D5_8") (pintype "bidirectional"))
      (node (ref "U2") (pin "9") (pinfunction "D4_9") (pintype "bidirectional"))
    )
    (net (code "41") (name "Net-(C8-Pad2)") (class "Default")
      (node (ref "C8") (pin "2") (pinfunction "2_2") (pintype "passive"))
      (node (ref "D1") (pin "ANODE") (pinfunction "ANODE_ANODE") (pintype "bidirectional"))
      (node (ref "R5") (pin "1") (pinfunction "1_1") (pintype "bidirectional"))
      (node (ref "R6") (pin "2") (pinfunction "2_2") (pintype "bidirectional"))
    )
    (net (code "42") (name "Net-(HC1-1:VCC)") (class "Default")
      (node (ref "HC1") (pin "1") (pinfunction "1:VCC_1") (pintype "bidirectional"))
      (node (ref "HC2") (pin "1") (pinfunction "1:VCC_1") (pintype "bidirectional"))
      (node (ref "HC3") (pin "1") (pinfunction "1:VCC_1") (pintype "bidirectional"))
      (node (ref "HC4") (pin "1") (pinfunction "1:VCC_1") (pintype "bidirectional"))
      (node (ref "HC5") (pin "1") (pinfunction "1:VCC_1") (pintype "bidirectional"))
      (node (ref "HC6") (pin "1") (pinfunction "1:VCC_1") (pintype "bidirectional"))
      (node (ref "HC7") (pin "1") (pinfunction "1:VCC_1") (pintype "bidirectional"))
      (node (ref "HC8") (pin "1") (pinfunction "1:VCC_1") (pintype "bidirectional"))
      (node (ref "JP1") (pin "2") (pinfunction "2_2") (pintype "passive"))
    )
    (net (code "43") (name "Net-(U2-BS1)") (class "Default")
      (node (ref "R6") (pin "1") (pinfunction "1_1") (pintype "bidirectional"))
      (node (ref "U2") (pin "17") (pinfunction "RES#_17") (pintype "bidirectional"))
      (node (ref "U2") (pin "20") (pinfunction "BS1_20") (pintype "bidirectional"))
    )
    (net (code "44") (name "Net-(U2-C1N)") (class "Default")
      (node (ref "C2") (pin "1") (pinfunction "1_1") (pintype "passive"))
      (node (ref "U2") (pin "26") (pinfunction "C1N_26") (pintype "bidirectional"))
    )
    (net (code "45") (name "Net-(U2-C1P)") (class "Default")
      (node (ref "C2") (pin "2") (pinfunction "2_2") (pintype "passive"))
      (node (ref "U2") (pin "27") (pinfunction "C1P_27") (pintype "bidirectional"))
    )
    (net (code "46") (name "Net-(U2-C2N)") (class "Default")
      (node (ref "C3") (pin "1") (pinfunction "1_1") (pintype "passive"))
      (node (ref "U2") (pin "28") (pinfunction "C2N_28") (pintype "bidirectional"))
    )
    (net (code "47") (name "Net-(U2-C2P)") (class "Default")
      (node (ref "C3") (pin "2") (pinfunction "2_2") (pintype "passive"))
      (node (ref "U2") (pin "29") (pinfunction "C2P_29") (pintype "bidirectional"))
    )
    (net (code "48") (name "Net-(U2-IREF)") (class "Default")
      (node (ref "R4") (pin "2") (pinfunction "2_2") (pintype "bidirectional"))
      (node (ref "U2") (pin "5") (pinfunction "IREF_5") (pintype "bidirectional"))
    )
    (net (code "49") (name "Net-(U2-VCC)") (class "Default")
      (node (ref "C7") (pin "2") (pinfunction "2_2") (pintype "passive"))
      (node (ref "U2") (pin "3") (pinfunction "VCC_3") (pintype "bidirectional"))
    )
    (net (code "50") (name "Net-(U2-VCOMH)") (class "Default")
      (node (ref "C6") (pin "2") (pinfunction "2_2") (pintype "passive"))
      (node (ref "U2") (pin "4") (pinfunction "VCOMH_4") (pintype "bidirectional"))
    )
    (net (code "51") (name "unconnected-(CON1-8:GPIO14(UART_TX)-Pad8)") (class "Default")
      (node (ref "CON1") (pin "8") (pinfunction "8:GPIO14(UART_TX)_8") (pintype "bidirectional"))
    )
    (net (code "52") (name "unconnected-(CON1-10:GPIO15(UART_RX)-Pad10)") (class "Default")
      (node (ref "CON1") (pin "10") (pinfunction "10:GPIO15(UART_RX)_10") (pintype "bidirectional"))
    )
    (net (code "53") (name "unconnected-(CON1-19:GPIO10(SPI_MOSI)-Pad19)") (class "Default")
      (node (ref "CON1") (pin "19") (pinfunction "19:GPIO10(SPI_MOSI)_19") (pintype "bidirectional"))
    )
    (net (code "54") (name "unconnected-(CON1-21:GPIO9(SPI_MISO)-Pad21)") (class "Default")
      (node (ref "CON1") (pin "21") (pinfunction "21:GPIO9(SPI_MISO)_21") (pintype "bidirectional"))
    )
    (net (code "55") (name "unconnected-(CON1-23:GPIO11(SPI_CLK)-Pad23)") (class "Default")
      (node (ref "CON1") (pin "23") (pinfunction "23:GPIO11(SPI_CLK)_23") (pintype "bidirectional"))
    )
    (net (code "56") (name "unconnected-(CON1-24:GPIO8(SPI_CE0_N)-Pad24)") (class "Default")
      (node (ref "CON1") (pin "24") (pinfunction "24:GPIO8(SPI_CE0_N)_24") (pintype "bidirectional"))
    )
    (net (code "57") (name "unconnected-(CON1-26:GPIO7(SPI_CE1_N)-Pad26)") (class "Default")
      (node (ref "CON1") (pin "26") (pinfunction "26:GPIO7(SPI_CE1_N)_26") (pintype "bidirectional"))
    )
    (net (code "58") (name "unconnected-(CON1-27:GPIO0(I2C,EEPROM_SDA)-Pad27)") (class "Default")
      (node (ref "CON1") (pin "27") (pinfunction "27:GPIO0(I2C,EEPROM_SDA)_27") (pintype "bidirectional"))
    )
    (net (code "59") (name "unconnected-(CON1-28:GPIO1(I2C,EEPROM_SCL)-Pad28)") (class "Default")
      (node (ref "CON1") (pin "28") (pinfunction "28:GPIO1(I2C,EEPROM_SCL)_28") (pintype "bidirectional"))
    )
    (net (code "60") (name "unconnected-(IC1-LED2-Pad8)") (class "Default")
      (node (ref "IC1") (pin "8") (pinfunction "LED2_8") (pintype "bidirectional"))
    )
    (net (code "61") (name "unconnected-(IC1-LED3-Pad9)") (class "Default")
      (node (ref "IC1") (pin "9") (pinfunction "LED3_9") (pintype "bidirectional"))
    )
    (net (code "62") (name "unconnected-(IC1-LED4-Pad10)") (class "Default")
      (node (ref "IC1") (pin "10") (pinfunction "LED4_10") (pintype "bidirectional"))
    )
    (net (code "63") (name "unconnected-(IC1-LED5-Pad11)") (class "Default")
      (node (ref "IC1") (pin "11") (pinfunction "LED5_11") (pintype "bidirectional"))
    )
    (net (code "64") (name "unconnected-(IC1-LED6-Pad12)") (class "Default")
      (node (ref "IC1") (pin "12") (pinfunction "LED6_12") (pintype "bidirectional"))
    )
    (net (code "65") (name "unconnected-(IC1-LED7-Pad13)") (class "Default")
      (node (ref "IC1") (pin "13") (pinfunction "LED7_13") (pintype "bidirectional"))
    )
    (net (code "66") (name "unconnected-(IC1-LED8-Pad15)") (class "Default")
      (node (ref "IC1") (pin "15") (pinfunction "LED8_15") (pintype "bidirectional"))
    )
    (net (code "67") (name "unconnected-(IC1-LED9-Pad16)") (class "Default")
      (node (ref "IC1") (pin "16") (pinfunction "LED9_16") (pintype "bidirectional"))
    )
    (net (code "68") (name "unconnected-(IC1-LED10-Pad17)") (class "Default")
      (node (ref "IC1") (pin "17") (pinfunction "LED10_17") (pintype "bidirectional"))
    )
    (net (code "69") (name "unconnected-(IC1-LED11-Pad18)") (class "Default")
      (node (ref "IC1") (pin "18") (pinfunction "LED11_18") (pintype "bidirectional"))
    )
    (net (code "70") (name "unconnected-(IC1-LED12-Pad19)") (class "Default")
      (node (ref "IC1") (pin "19") (pinfunction "LED12_19") (pintype "bidirectional"))
    )
    (net (code "71") (name "unconnected-(IC1-LED13-Pad20)") (class "Default")
      (node (ref "IC1") (pin "20") (pinfunction "LED13_20") (pintype "bidirectional"))
    )
    (net (code "72") (name "unconnected-(IC1-LED14-Pad21)") (class "Default")
      (node (ref "IC1") (pin "21") (pinfunction "LED14_21") (pintype "bidirectional"))
    )
    (net (code "73") (name "unconnected-(IC1-LED15-Pad22)") (class "Default")
      (node (ref "IC1") (pin "22") (pinfunction "LED15_22") (pintype "bidirectional"))
    )
    (net (code "74") (name "unconnected-(U2-NC-Pad1)") (class "Default")
      (node (ref "U2") (pin "1") (pinfunction "NC_1") (pintype "bidirectional"))
    )
    (net (code "75") (name "unconnected-(U2-NC-Pad24)") (class "Default")
      (node (ref "U2") (pin "24") (pinfunction "NC_24") (pintype "bidirectional"))
    )
    (net (code "76") (name "unconnected-(U2-NC-Pad30)") (class "Default")
      (node (ref "U2") (pin "30") (pinfunction "NC_30") (pintype "bidirectional"))
    )
  )
)
